# Charger_Module.net
KiCad netlist of a schematic drawn in Altium Designer
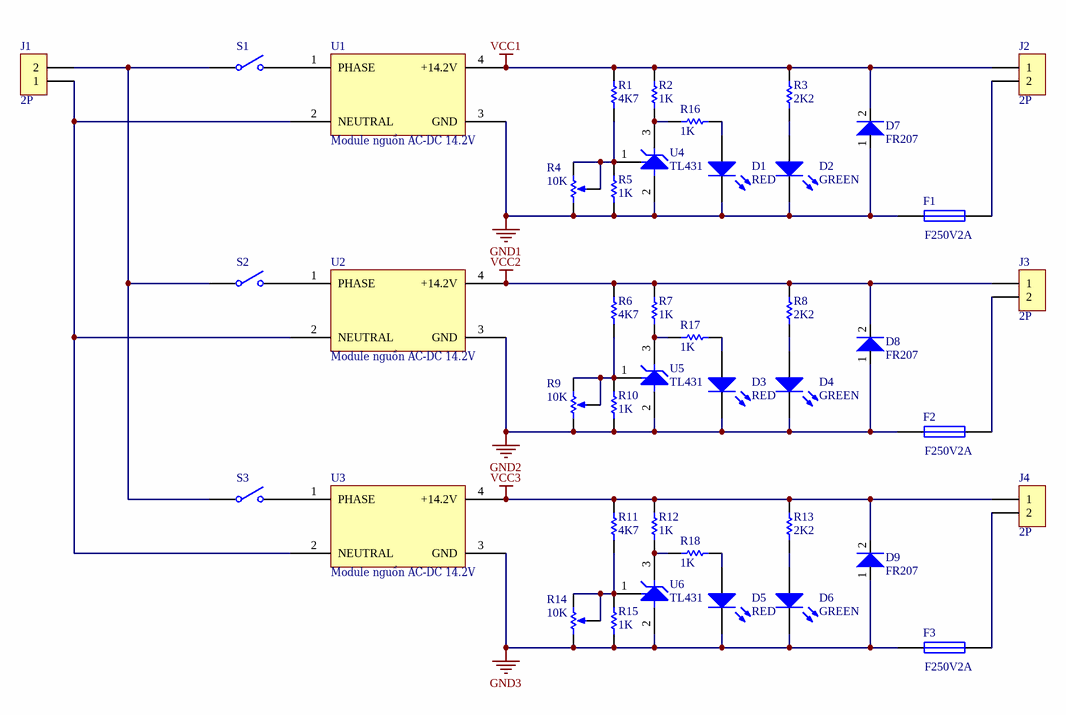
[diagram p0: Charger Module.SchDoc]

(export (version "E")
  (design (tool "Eeschema 10.0.6"))
  (components
    (comp (ref "D1")
      (value "RED")
      (footprint "LED-0")
      (description "Typical INFRARED GaAs LED")
      (fields (field (name "Comment") "LED chân cắm 5mmRED") (field (name "PUBLISHER") "*"))
      (libsource (lib "DnsSchLib") (part "LED0"))
    )
    (comp (ref "D2")
      (value "GREEN")
      (footprint "LED-0")
      (description "Typical INFRARED GaAs LED")
      (fields (field (name "Comment") "LED chân cắm 5mmGREEN") (field (name "PUBLISHER") "*"))
      (libsource (lib "DnsSchLib") (part "LED0"))
    )
    (comp (ref "D3")
      (value "RED")
      (footprint "LED-0")
      (description "Typical INFRARED GaAs LED")
      (fields (field (name "Comment") "LED chân cắm 5mmRED") (field (name "PUBLISHER") "*"))
      (libsource (lib "DnsSchLib") (part "LED0"))
    )
    (comp (ref "D4")
      (value "GREEN")
      (footprint "LED-0")
      (description "Typical INFRARED GaAs LED")
      (fields (field (name "Comment") "LED chân cắm 5mmGREEN") (field (name "PUBLISHER") "*"))
      (libsource (lib "DnsSchLib") (part "LED0"))
    )
    (comp (ref "D5")
      (value "RED")
      (footprint "LED-0")
      (description "Typical INFRARED GaAs LED")
      (fields (field (name "Comment") "LED chân cắm 5mmRED") (field (name "PUBLISHER") "*"))
      (libsource (lib "DnsSchLib") (part "LED0"))
    )
    (comp (ref "D6")
      (value "GREEN")
      (footprint "LED-0")
      (description "Typical INFRARED GaAs LED")
      (fields (field (name "Comment") "LED chân cắm 5mmGREEN") (field (name "PUBLISHER") "*"))
      (libsource (lib "DnsSchLib") (part "LED0"))
    )
    (comp (ref "D7")
      (value "FR207")
      (footprint "DIODE1A")
      (fields (field (name "Comment") "Diode xung chân cắm 2AFR207"))
      (libsource (lib "DnsSchLib") (part "DIODE"))
    )
    (comp (ref "D8")
      (value "FR207")
      (footprint "DIODE1A")
      (fields (field (name "Comment") "Diode xung chân cắm 2AFR207"))
      (libsource (lib "DnsSchLib") (part "DIODE"))
    )
    (comp (ref "D9")
      (value "FR207")
      (footprint "DIODE1A")
      (fields (field (name "Comment") "Diode xung chân cắm 2AFR207"))
      (libsource (lib "DnsSchLib") (part "DIODE"))
    )
    (comp (ref "F1")
      (value "F250V2A")
      (footprint "FUSE2")
      (description "Fuse")
      (fields
        (field (name "Comment") "Cầu chì và đế cầu chìF250V2A")
        (field (name "PUBLISHER") "Altium Limited")
      )
      (libsource (lib "Miscellaneous Devices") (part "Fuse 1"))
    )
    (comp (ref "F2")
      (value "F250V2A")
      (footprint "FUSE2")
      (description "Fuse")
      (fields
        (field (name "Comment") "Cầu chì và đế cầu chìF250V2A")
        (field (name "PUBLISHER") "Altium Limited")
      )
      (libsource (lib "Miscellaneous Devices") (part "Fuse 1"))
    )
    (comp (ref "F3")
      (value "F250V2A")
      (footprint "FUSE2")
      (description "Fuse")
      (fields
        (field (name "Comment") "Cầu chì và đế cầu chìF250V2A")
        (field (name "PUBLISHER") "Altium Limited")
      )
      (libsource (lib "Miscellaneous Devices") (part "Fuse 1"))
    )
    (comp (ref "J1")
      (value "2P")
      (footprint "JACK2")
      (fields (field (name "Comment") "Giắc xanh loại đứng, 300V/16A - 5.08mm 2P"))
      (libsource (lib "") (part "CON2_1"))
    )
    (comp (ref "J2")
      (value "2P")
      (footprint "JACK2")
      (fields (field (name "Comment") "Giắc xanh loại đứng, 300V/16A - 5.08mm 2P"))
      (libsource (lib "DnsSchLib") (part "CON2"))
    )
    (comp (ref "J3")
      (value "2P")
      (footprint "JACK2")
      (fields (field (name "Comment") "Giắc xanh loại đứng, 300V/16A - 5.08mm 2P"))
      (libsource (lib "DnsSchLib") (part "CON2"))
    )
    (comp (ref "J4")
      (value "2P")
      (footprint "JACK2")
      (fields (field (name "Comment") "Giắc xanh loại đứng, 300V/16A - 5.08mm 2P"))
      (libsource (lib "DnsSchLib") (part "CON2"))
    )
    (comp (ref "R1")
      (value "4K7")
      (footprint "0805DD")
      (description "Semiconductor Resistor")
      (fields (field (name "Comment") "Điện trở dán 08054K7") (field (name "PUBLISHER") "*"))
      (libsource (lib "DnsSchLib") (part "Res Semi"))
    )
    (comp (ref "R2")
      (value "1K")
      (footprint "0805DD")
      (description "Semiconductor Resistor")
      (fields (field (name "Comment") "Điện trở dán 08051K") (field (name "PUBLISHER") "*"))
      (libsource (lib "DnsSchLib") (part "Res Semi"))
    )
    (comp (ref "R3")
      (value "2K2")
      (footprint "0805DD")
      (description "Semiconductor Resistor")
      (fields (field (name "Comment") "Điện trở dán 08052K2") (field (name "PUBLISHER") "*"))
      (libsource (lib "DnsSchLib") (part "Res Semi"))
    )
    (comp (ref "R4")
      (value "10K")
      (footprint "BTXANH")
      (description "Potentiometer")
      (fields (field (name "Comment") "Biến trở vi chỉnh TRIMMER 329610K") (field (name "PUBLISHER") "*"))
      (libsource (lib "DnsSchLib") (part "RPot"))
    )
    (comp (ref "R5")
      (value "1K")
      (footprint "0805DD")
      (description "Semiconductor Resistor")
      (fields (field (name "Comment") "Điện trở dán 08051K") (field (name "PUBLISHER") "*"))
      (libsource (lib "DnsSchLib") (part "Res Semi"))
    )
    (comp (ref "R6")
      (value "4K7")
      (footprint "0805DD")
      (description "Semiconductor Resistor")
      (fields (field (name "Comment") "Điện trở dán 08054K7") (field (name "PUBLISHER") "*"))
      (libsource (lib "DnsSchLib") (part "Res Semi"))
    )
    (comp (ref "R7")
      (value "1K")
      (footprint "0805DD")
      (description "Semiconductor Resistor")
      (fields (field (name "Comment") "Điện trở dán 08051K") (field (name "PUBLISHER") "*"))
      (libsource (lib "DnsSchLib") (part "Res Semi"))
    )
    (comp (ref "R8")
      (value "2K2")
      (footprint "0805DD")
      (description "Semiconductor Resistor")
      (fields (field (name "Comment") "Điện trở dán 08052K2") (field (name "PUBLISHER") "*"))
      (libsource (lib "DnsSchLib") (part "Res Semi"))
    )
    (comp (ref "R9")
      (value "10K")
      (footprint "BTXANH")
      (description "Potentiometer")
      (fields (field (name "Comment") "Biến trở vi chỉnh TRIMMER 329610K") (field (name "PUBLISHER") "*"))
      (libsource (lib "DnsSchLib") (part "RPot"))
    )
    (comp (ref "R10")
      (value "1K")
      (footprint "0805DD")
      (description "Semiconductor Resistor")
      (fields (field (name "Comment") "Điện trở dán 08051K") (field (name "PUBLISHER") "*"))
      (libsource (lib "DnsSchLib") (part "Res Semi"))
    )
    (comp (ref "R11")
      (value "4K7")
      (footprint "0805DD")
      (description "Semiconductor Resistor")
      (fields (field (name "Comment") "Điện trở dán 08054K7") (field (name "PUBLISHER") "*"))
      (libsource (lib "DnsSchLib") (part "Res Semi"))
    )
    (comp (ref "R12")
      (value "1K")
      (footprint "0805DD")
      (description "Semiconductor Resistor")
      (fields (field (name "Comment") "Điện trở dán 08051K") (field (name "PUBLISHER") "*"))
      (libsource (lib "DnsSchLib") (part "Res Semi"))
    )
    (comp (ref "R13")
      (value "2K2")
      (footprint "0805DD")
      (description "Semiconductor Resistor")
      (fields (field (name "Comment") "Điện trở dán 08052K2") (field (name "PUBLISHER") "*"))
      (libsource (lib "DnsSchLib") (part "Res Semi"))
    )
    (comp (ref "R14")
      (value "10K")
      (footprint "BTXANH")
      (description "Potentiometer")
      (fields (field (name "Comment") "Biến trở vi chỉnh TRIMMER 329610K") (field (name "PUBLISHER") "*"))
      (libsource (lib "DnsSchLib") (part "RPot"))
    )
    (comp (ref "R15")
      (value "1K")
      (footprint "0805DD")
      (description "Semiconductor Resistor")
      (fields (field (name "Comment") "Điện trở dán 08051K") (field (name "PUBLISHER") "*"))
      (libsource (lib "DnsSchLib") (part "Res Semi"))
    )
    (comp (ref "R16")
      (value "1K")
      (footprint "0805DD")
      (description "Semiconductor Resistor")
      (fields (field (name "Comment") "Điện trở dán 08051K") (field (name "PUBLISHER") "*"))
      (libsource (lib "DnsSchLib") (part "Res Semi"))
    )
    (comp (ref "R17")
      (value "1K")
      (footprint "0805DD")
      (description "Semiconductor Resistor")
      (fields (field (name "Comment") "Điện trở dán 08051K") (field (name "PUBLISHER") "*"))
      (libsource (lib "DnsSchLib") (part "Res Semi"))
    )
    (comp (ref "R18")
      (value "1K")
      (footprint "0805DD")
      (description "Semiconductor Resistor")
      (fields (field (name "Comment") "Điện trở dán 08051K") (field (name "PUBLISHER") "*"))
      (libsource (lib "DnsSchLib") (part "Res Semi"))
    )
    (comp (ref "S1")
      (value "Giắc cắm loại đứng, 300V/16A - 5.08mm 2P")
      (footprint "JACK2")
      (description "Single-Pole, Single-Throw Switch")
      (fields (field (name "PUBLISHER") "Altium Limited"))
      (libsource (lib "Miscellaneous Devices") (part "SW-SPST"))
    )
    (comp (ref "S2")
      (value "Giắc cắm loại đứng, 300V/16A - 5.08mm 2P")
      (footprint "JACK2")
      (description "Single-Pole, Single-Throw Switch")
      (fields (field (name "PUBLISHER") "Altium Limited"))
      (libsource (lib "Miscellaneous Devices") (part "SW-SPST"))
    )
    (comp (ref "S3")
      (value "Giắc cắm loại đứng, 300V/16A - 5.08mm 2P")
      (footprint "JACK2")
      (description "Single-Pole, Single-Throw Switch")
      (fields (field (name "PUBLISHER") "Altium Limited"))
      (libsource (lib "Miscellaneous Devices") (part "SW-SPST"))
    )
    (comp (ref "U1")
      (value "Module nguồn AC-DC 14.2V")
      (footprint "PS15V2A")
      (libsource (lib "DnsSchLib") (part "SACACQUY"))
    )
    (comp (ref "U2")
      (value "Module nguồn AC-DC 14.2V")
      (footprint "PS15V2A")
      (libsource (lib "DnsSchLib") (part "SACACQUY"))
    )
    (comp (ref "U3")
      (value "Module nguồn AC-DC 14.2V")
      (footprint "PS15V2A")
      (libsource (lib "DnsSchLib") (part "SACACQUY"))
    )
    (comp (ref "U4")
      (value "TL431")
      (footprint "TO92_431")
      (description "Adjustable Precision Shunt Regulator")
      (fields (field (name "Comment") "IC điện áp chuẩn, chân cắm TO92TL431"))
      (libsource (lib "DnsSchLib") (part "TL431"))
    )
    (comp (ref "U5")
      (value "TL431")
      (footprint "TO92_431")
      (description "Adjustable Precision Shunt Regulator")
      (fields (field (name "Comment") "IC điện áp chuẩn, chân cắm TO92TL431"))
      (libsource (lib "DnsSchLib") (part "TL431"))
    )
    (comp (ref "U6")
      (value "TL431")
      (footprint "TO92_431")
      (description "Adjustable Precision Shunt Regulator")
      (fields (field (name "Comment") "IC điện áp chuẩn, chân cắm TO92TL431"))
      (libsource (lib "DnsSchLib") (part "TL431"))
    )
  )
  (nets
    (net (code "1") (name "GND1") (class "Default")
      (node (ref "D1") (pin "2") (pinfunction "K_2") (pintype "passive"))
      (node (ref "D2") (pin "2") (pinfunction "K_2") (pintype "passive"))
      (node (ref "D7") (pin "1") (pinfunction "A_1") (pintype "passive"))
      (node (ref "F1") (pin "1") (pinfunction "1_1") (pintype "passive"))
      (node (ref "R4") (pin "1") (pinfunction "TOP_1") (pintype "passive"))
      (node (ref "R5") (pin "1") (pinfunction "1_1") (pintype "passive"))
      (node (ref "U1") (pin "3") (pinfunction "GND_3") (pintype "passive"))
      (node (ref "U4") (pin "2") (pinfunction "A_2") (pintype "passive"))
    )
    (net (code "2") (name "GND2") (class "Default")
      (node (ref "D3") (pin "2") (pinfunction "K_2") (pintype "passive"))
      (node (ref "D4") (pin "2") (pinfunction "K_2") (pintype "passive"))
      (node (ref "D8") (pin "1") (pinfunction "A_1") (pintype "passive"))
      (node (ref "F2") (pin "1") (pinfunction "1_1") (pintype "passive"))
      (node (ref "R10") (pin "1") (pinfunction "1_1") (pintype "passive"))
      (node (ref "R9") (pin "1") (pinfunction "TOP_1") (pintype "passive"))
      (node (ref "U2") (pin "3") (pinfunction "GND_3") (pintype "passive"))
      (node (ref "U5") (pin "2") (pinfunction "A_2") (pintype "passive"))
    )
    (net (code "3") (name "GND3") (class "Default")
      (node (ref "D5") (pin "2") (pinfunction "K_2") (pintype "passive"))
      (node (ref "D6") (pin "2") (pinfunction "K_2") (pintype "passive"))
      (node (ref "D9") (pin "1") (pinfunction "A_1") (pintype "passive"))
      (node (ref "F3") (pin "1") (pinfunction "1_1") (pintype "passive"))
      (node (ref "R14") (pin "1") (pinfunction "TOP_1") (pintype "passive"))
      (node (ref "R15") (pin "1") (pinfunction "1_1") (pintype "passive"))
      (node (ref "U3") (pin "3") (pinfunction "GND_3") (pintype "passive"))
      (node (ref "U6") (pin "2") (pinfunction "A_2") (pintype "passive"))
    )
    (net (code "4") (name "Net-(D1-A)") (class "Default")
      (node (ref "D1") (pin "1") (pinfunction "A_1") (pintype "passive"))
      (node (ref "R16") (pin "1") (pinfunction "1_1") (pintype "passive"))
    )
    (net (code "5") (name "Net-(D2-A)") (class "Default")
      (node (ref "D2") (pin "1") (pinfunction "A_1") (pintype "passive"))
      (node (ref "R3") (pin "1") (pinfunction "1_1") (pintype "passive"))
    )
    (net (code "6") (name "Net-(D3-A)") (class "Default")
      (node (ref "D3") (pin "1") (pinfunction "A_1") (pintype "passive"))
      (node (ref "R17") (pin "1") (pinfunction "1_1") (pintype "passive"))
    )
    (net (code "7") (name "Net-(D4-A)") (class "Default")
      (node (ref "D4") (pin "1") (pinfunction "A_1") (pintype "passive"))
      (node (ref "R8") (pin "1") (pinfunction "1_1") (pintype "passive"))
    )
    (net (code "8") (name "Net-(D5-A)") (class "Default")
      (node (ref "D5") (pin "1") (pinfunction "A_1") (pintype "passive"))
      (node (ref "R18") (pin "1") (pinfunction "1_1") (pintype "passive"))
    )
    (net (code "9") (name "Net-(D6-A)") (class "Default")
      (node (ref "D6") (pin "1") (pinfunction "A_1") (pintype "passive"))
      (node (ref "R13") (pin "1") (pinfunction "1_1") (pintype "passive"))
    )
    (net (code "10") (name "Net-(F1-Pad2)") (class "Default")
      (node (ref "F1") (pin "2") (pinfunction "2_2") (pintype "passive"))
      (node (ref "J2") (pin "2") (pinfunction "2_2") (pintype "passive"))
    )
    (net (code "11") (name "Net-(F2-Pad2)") (class "Default")
      (node (ref "F2") (pin "2") (pinfunction "2_2") (pintype "passive"))
      (node (ref "J3") (pin "2") (pinfunction "2_2") (pintype "passive"))
    )
    (net (code "12") (name "Net-(F3-Pad2)") (class "Default")
      (node (ref "F3") (pin "2") (pinfunction "2_2") (pintype "passive"))
      (node (ref "J4") (pin "2") (pinfunction "2_2") (pintype "passive"))
    )
    (net (code "13") (name "Net-(R4-BOT)") (class "Default")
      (node (ref "R1") (pin "2") (pinfunction "2_2") (pintype "passive"))
      (node (ref "R4") (pin "2") (pinfunction "TAP_2") (pintype "passive"))
      (node (ref "R4") (pin "3") (pinfunction "BOT_3") (pintype "passive"))
      (node (ref "R5") (pin "2") (pinfunction "2_2") (pintype "passive"))
      (node (ref "U4") (pin "1") (pinfunction "R_1") (pintype "passive"))
    )
    (net (code "14") (name "Net-(R9-BOT)") (class "Default")
      (node (ref "R10") (pin "2") (pinfunction "2_2") (pintype "passive"))
      (node (ref "R6") (pin "2") (pinfunction "2_2") (pintype "passive"))
      (node (ref "R9") (pin "2") (pinfunction "TAP_2") (pintype "passive"))
      (node (ref "R9") (pin "3") (pinfunction "BOT_3") (pintype "passive"))
      (node (ref "U5") (pin "1") (pinfunction "R_1") (pintype "passive"))
    )
    (net (code "15") (name "Net-(R14-BOT)") (class "Default")
      (node (ref "R11") (pin "2") (pinfunction "2_2") (pintype "passive"))
      (node (ref "R14") (pin "2") (pinfunction "TAP_2") (pintype "passive"))
      (node (ref "R14") (pin "3") (pinfunction "BOT_3") (pintype "passive"))
      (node (ref "R15") (pin "2") (pinfunction "2_2") (pintype "passive"))
      (node (ref "U6") (pin "1") (pinfunction "R_1") (pintype "passive"))
    )
    (net (code "16") (name "Net-(S1-COMMON)") (class "Default")
      (node (ref "J1") (pin "2") (pinfunction "2_2") (pintype "passive"))
      (node (ref "S1") (pin "1") (pinfunction "COMMON_1") (pintype "passive"))
      (node (ref "S2") (pin "1") (pinfunction "COMMON_1") (pintype "passive"))
      (node (ref "S3") (pin "1") (pinfunction "COMMON_1") (pintype "passive"))
    )
    (net (code "17") (name "Net-(S1-NO)") (class "Default")
      (node (ref "S1") (pin "2") (pinfunction "NO_2") (pintype "passive"))
      (node (ref "U1") (pin "1") (pinfunction "PHASE_1") (pintype "passive"))
    )
    (net (code "18") (name "Net-(S2-NO)") (class "Default")
      (node (ref "S2") (pin "2") (pinfunction "NO_2") (pintype "passive"))
      (node (ref "U2") (pin "1") (pinfunction "PHASE_1") (pintype "passive"))
    )
    (net (code "19") (name "Net-(S3-NO)") (class "Default")
      (node (ref "S3") (pin "2") (pinfunction "NO_2") (pintype "passive"))
      (node (ref "U3") (pin "1") (pinfunction "PHASE_1") (pintype "passive"))
    )
    (net (code "20") (name "Net-(U1-NEUTRAL)") (class "Default")
      (node (ref "J1") (pin "1") (pinfunction "1_1") (pintype "passive"))
      (node (ref "U1") (pin "2") (pinfunction "NEUTRAL_2") (pintype "passive"))
      (node (ref "U2") (pin "2") (pinfunction "NEUTRAL_2") (pintype "passive"))
      (node (ref "U3") (pin "2") (pinfunction "NEUTRAL_2") (pintype "passive"))
    )
    (net (code "21") (name "Net-(U4-K)") (class "Default")
      (node (ref "R16") (pin "2") (pinfunction "2_2") (pintype "passive"))
      (node (ref "R2") (pin "1") (pinfunction "1_1") (pintype "passive"))
      (node (ref "U4") (pin "3") (pinfunction "K_3") (pintype "passive"))
    )
    (net (code "22") (name "Net-(U5-K)") (class "Default")
      (node (ref "R17") (pin "2") (pinfunction "2_2") (pintype "passive"))
      (node (ref "R7") (pin "1") (pinfunction "1_1") (pintype "passive"))
      (node (ref "U5") (pin "3") (pinfunction "K_3") (pintype "passive"))
    )
    (net (code "23") (name "Net-(U6-K)") (class "Default")
      (node (ref "R12") (pin "1") (pinfunction "1_1") (pintype "passive"))
      (node (ref "R18") (pin "2") (pinfunction "2_2") (pintype "passive"))
      (node (ref "U6") (pin "3") (pinfunction "K_3") (pintype "passive"))
    )
    (net (code "24") (name "VCC1") (class "Default")
      (node (ref "D7") (pin "2") (pinfunction "K_2") (pintype "passive"))
      (node (ref "J2") (pin "1") (pinfunction "1_1") (pintype "passive"))
      (node (ref "R1") (pin "1") (pinfunction "1_1") (pintype "passive"))
      (node (ref "R2") (pin "2") (pinfunction "2_2") (pintype "passive"))
      (node (ref "R3") (pin "2") (pinfunction "2_2") (pintype "passive"))
      (node (ref "U1") (pin "4") (pinfunction "+14.2V_4") (pintype "passive"))
    )
    (net (code "25") (name "VCC2") (class "Default")
      (node (ref "D8") (pin "2") (pinfunction "K_2") (pintype "passive"))
      (node (ref "J3") (pin "1") (pinfunction "1_1") (pintype "passive"))
      (node (ref "R6") (pin "1") (pinfunction "1_1") (pintype "passive"))
      (node (ref "R7") (pin "2") (pinfunction "2_2") (pintype "passive"))
      (node (ref "R8") (pin "2") (pinfunction "2_2") (pintype "passive"))
      (node (ref "U2") (pin "4") (pinfunction "+14.2V_4") (pintype "passive"))
    )
    (net (code "26") (name "VCC3") (class "Default")
      (node (ref "D9") (pin "2") (pinfunction "K_2") (pintype "passive"))
      (node (ref "J4") (pin "1") (pinfunction "1_1") (pintype "passive"))
      (node (ref "R11") (pin "1") (pinfunction "1_1") (pintype "passive"))
      (node (ref "R12") (pin "2") (pinfunction "2_2") (pintype "passive"))
      (node (ref "R13") (pin "2") (pinfunction "2_2") (pintype "passive"))
      (node (ref "U3") (pin "4") (pinfunction "+14.2V_4") (pintype "passive"))
    )
  )
)
